# NRC7394-RX.net
KiCad netlist of a schematic drawn in Altium Designer
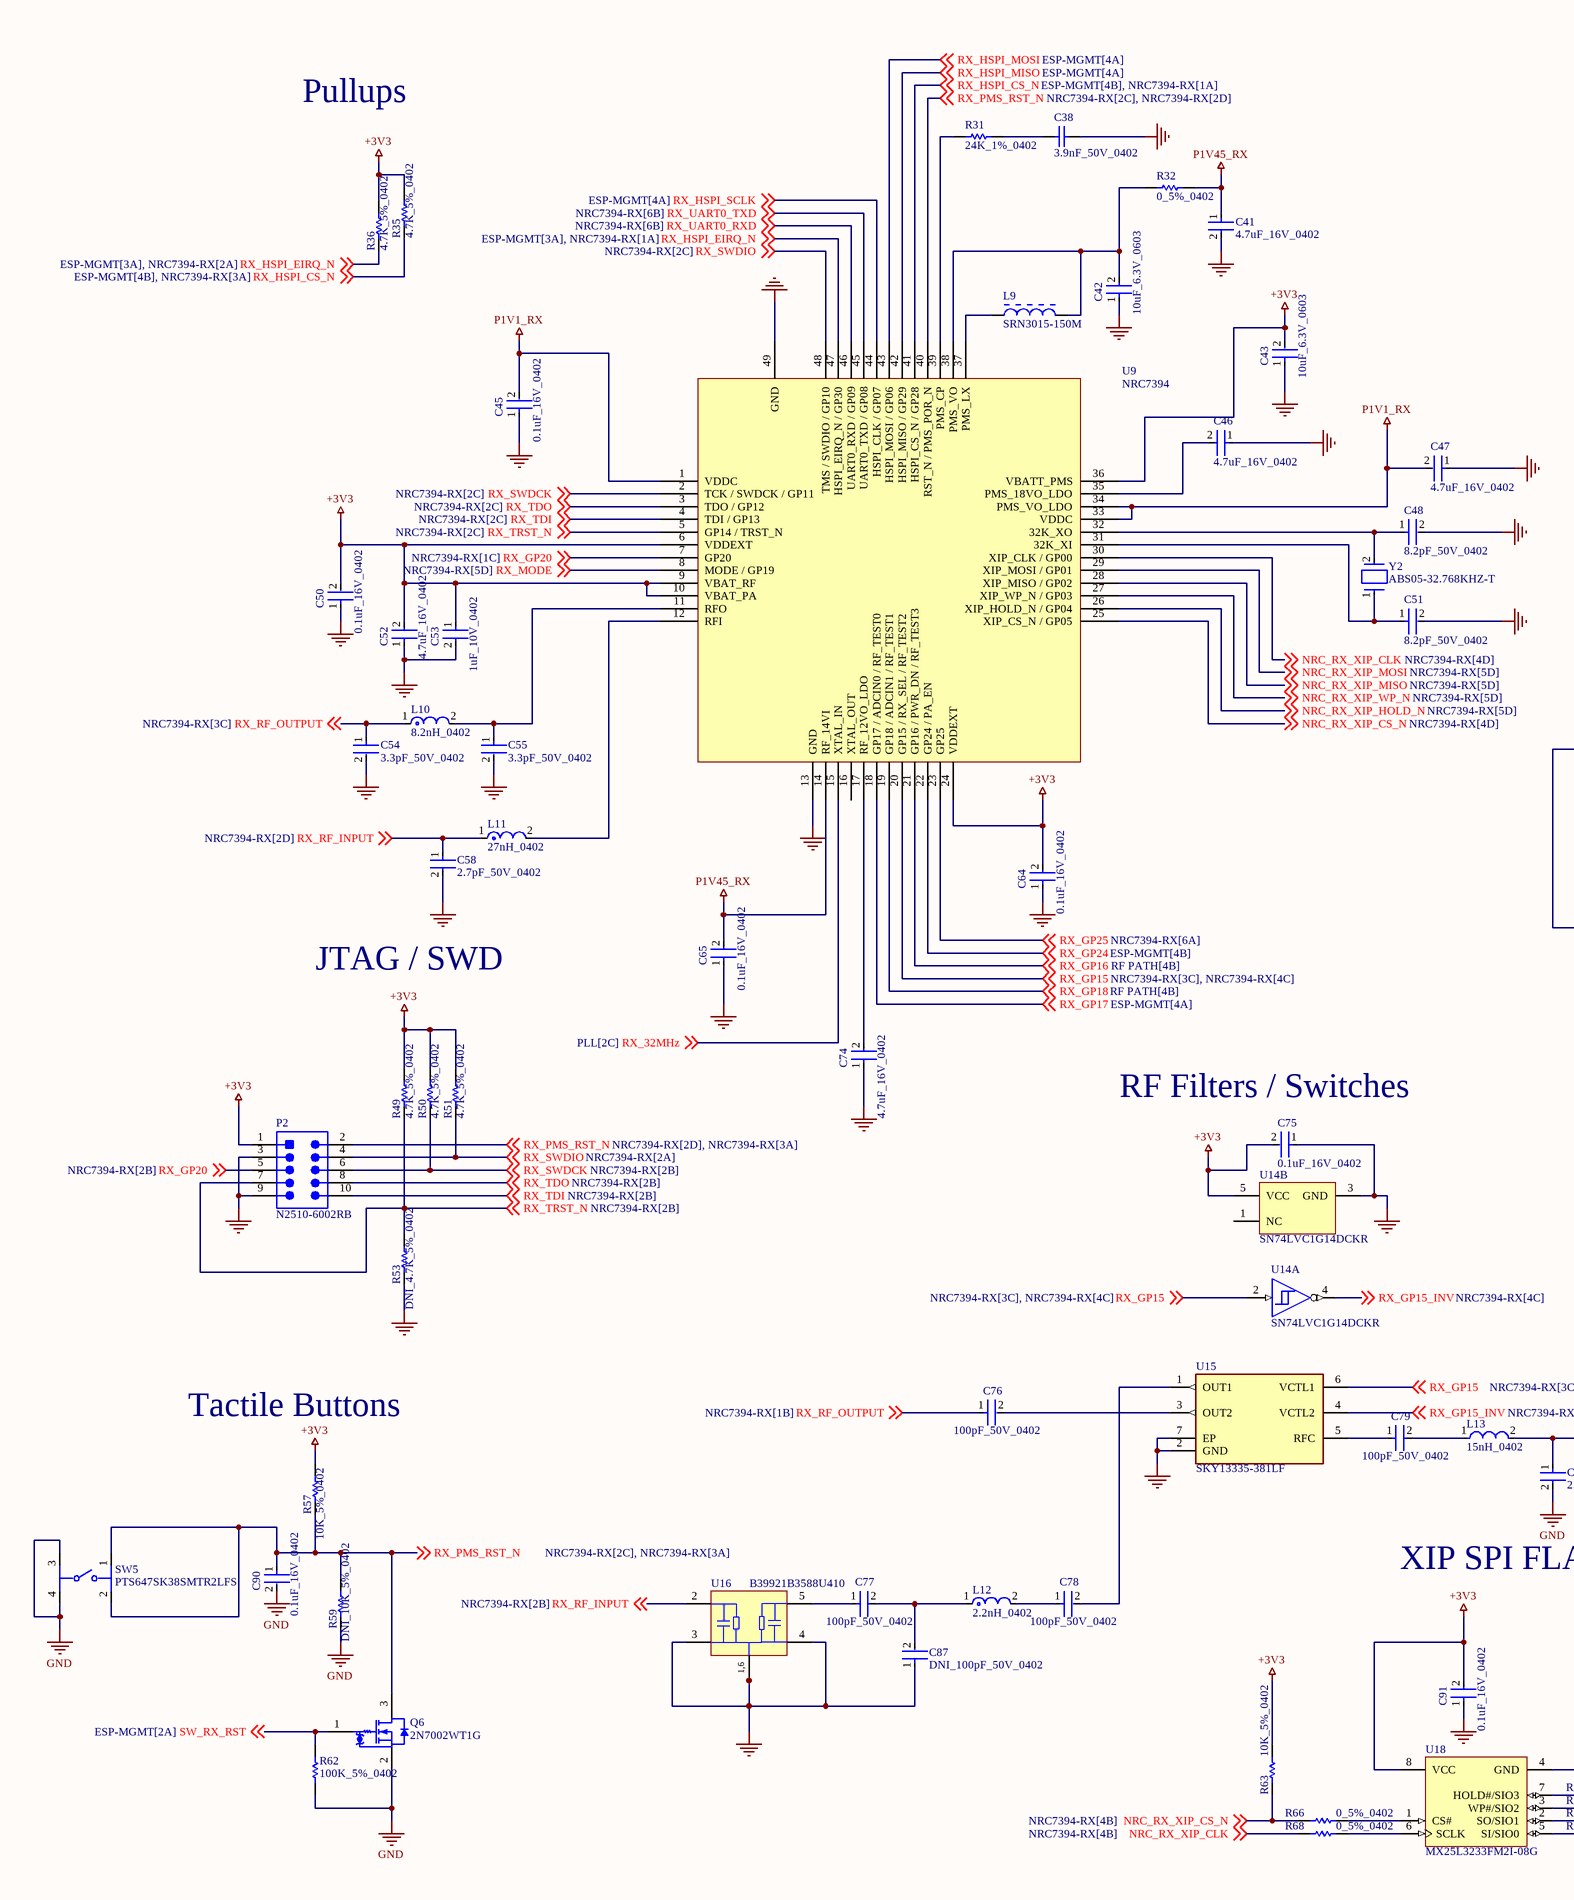
[diagram p0: NRC7394-RX.SchDoc, left]
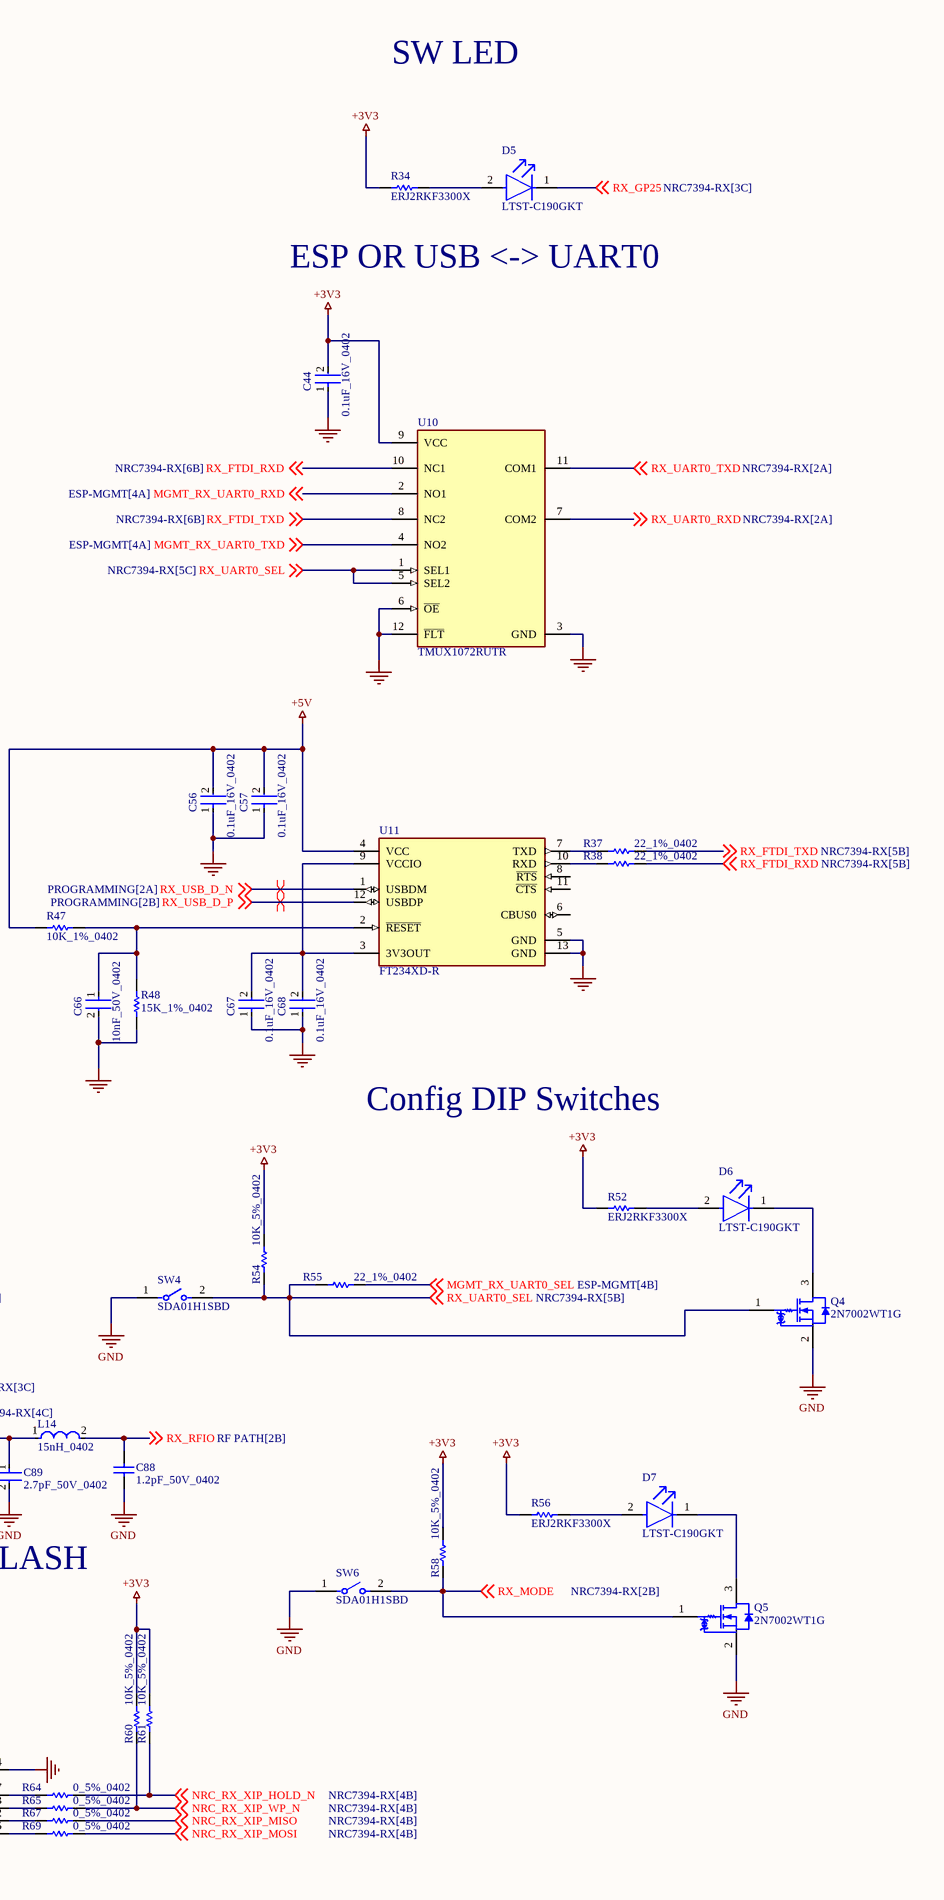
[diagram p1: NRC7394-RX.SchDoc, right]

(export (version "E")
  (design (tool "Eeschema 10.0.6"))
  (components
    (comp (ref "C38")
      (value "3.9nF_50V_0402")
      (footprint "CAPC1005X56X25LL10T15")
      (fields
        (field (name "MANUFACTURER") "AVX Interconnect / Elco")
        (field (name "PART NUMBER") "04025C392JAT2A")
      )
      (libsource (lib "Altium Content Vault") (part "CAP"))
    )
    (comp (ref "C41")
      (value "4.7uF_16V_0402")
      (footprint "FP-CL829-IPC_C")
      (description "Cap Ceramic 4.7uF 16V X5R ±20% SMD 0402 +85°C Paper T/R")
      (fields (field (name "TOLERANCE") "20%"))
      (libsource (lib "Altium Content Vault") (part "b4654b650e69147ec39a6b967a45e02"))
    )
    (comp (ref "C42")
      (value "10uF_6.3V_0603")
      (footprint "FP-GRM188-0_1-e0_2_0_55-IPC_A")
      (description "Chip Multilayer Ceramic Capacitors for General Purpose, 0603, 10uF, X5R, 15%, 20%, 6.3V")
      (fields (field (name "VOLTAGE") "6.3V") (field (name "TOLERANCE") "20%"))
      (libsource (lib "Altium Content Vault") (part "02cd4be3c70576c341d710602a673aa"))
    )
    (comp (ref "C43")
      (value "10uF_6.3V_0603")
      (footprint "FP-GRM188-0_1-e0_2_0_55-IPC_A")
      (description "Chip Multilayer Ceramic Capacitors for General Purpose, 0603, 10uF, X5R, 15%, 20%, 6.3V")
      (fields (field (name "VOLTAGE") "6.3V") (field (name "TOLERANCE") "20%"))
      (libsource (lib "Altium Content Vault") (part "02cd4be3c70576c341d710602a673aa"))
    )
    (comp (ref "C44")
      (value "0.1uF_16V_0402")
      (footprint "FP-C0402-BB-MFG")
      (description "CAP CER 0.1UF 16V 20% X7R 0402")
      (fields
        (field (name "MANUFACTURER") "Kemet")
        (field (name "OCTOPART") "https://octopart.com/c0402c104m4ractu-kemet-10476575")
      )
      (libsource (lib "Altium Content Vault") (part "b4654b650e69147ec39a6b967a45e02"))
    )
    (comp (ref "C45")
      (value "0.1uF_16V_0402")
      (footprint "FP-C0402-BB-MFG")
      (description "CAP CER 0.1UF 16V 20% X7R 0402")
      (fields
        (field (name "MANUFACTURER") "Kemet")
        (field (name "OCTOPART") "https://octopart.com/c0402c104m4ractu-kemet-10476575")
      )
      (libsource (lib "Altium Content Vault") (part "b4654b650e69147ec39a6b967a45e02"))
    )
    (comp (ref "C46")
      (value "4.7uF_16V_0402")
      (footprint "FP-CL829-IPC_C")
      (description "Cap Ceramic 4.7uF 16V X5R ±20% SMD 0402 +85°C Paper T/R")
      (fields (field (name "TOLERANCE") "20%"))
      (libsource (lib "Altium Content Vault") (part "b4654b650e69147ec39a6b967a45e02"))
    )
    (comp (ref "C47")
      (value "4.7uF_16V_0402")
      (footprint "FP-CL829-IPC_C")
      (description "Cap Ceramic 4.7uF 16V X5R ±20% SMD 0402 +85°C Paper T/R")
      (fields (field (name "TOLERANCE") "20%"))
      (libsource (lib "Altium Content Vault") (part "b4654b650e69147ec39a6b967a45e02"))
    )
    (comp (ref "C48")
      (value "8.2pF_50V_0402")
      (footprint "FP-C0402-BB-MFG")
      (description "CAP CER 8.2PF 50V NP0 0402")
      (fields
        (field (name "MANUFACTURER PART NUMBER") "C0402C829C5GACTU")
        (field (name "TOLERANCE") "0.25 pF")
      )
      (libsource (lib "Altium Content Vault") (part "b4654b650e69147ec39a6b967a45e02"))
    )
    (comp (ref "C50")
      (value "0.1uF_16V_0402")
      (footprint "FP-C0402-BB-MFG")
      (description "CAP CER 0.1UF 16V 20% X7R 0402")
      (fields
        (field (name "MANUFACTURER") "Kemet")
        (field (name "OCTOPART") "https://octopart.com/c0402c104m4ractu-kemet-10476575")
      )
      (libsource (lib "Altium Content Vault") (part "b4654b650e69147ec39a6b967a45e02"))
    )
    (comp (ref "C51")
      (value "8.2pF_50V_0402")
      (footprint "FP-C0402-BB-MFG")
      (description "CAP CER 8.2PF 50V NP0 0402")
      (fields
        (field (name "MANUFACTURER PART NUMBER") "C0402C829C5GACTU")
        (field (name "TOLERANCE") "0.25 pF")
      )
      (libsource (lib "Altium Content Vault") (part "b4654b650e69147ec39a6b967a45e02"))
    )
    (comp (ref "C52")
      (value "4.7uF_16V_0402")
      (footprint "FP-CL829-IPC_C")
      (description "Cap Ceramic 4.7uF 16V X5R ±20% SMD 0402 +85°C Paper T/R")
      (fields (field (name "TOLERANCE") "20%"))
      (libsource (lib "Altium Content Vault") (part "b4654b650e69147ec39a6b967a45e02"))
    )
    (comp (ref "C53")
      (value "1uF_10V_0402")
      (footprint "FP-C0402C105K8PACTU-MFG")
      (description "CAP CER 1UF 10V X5R 0402")
      (fields (field (name "VOLTAGE") "10V") (field (name "TOLERANCE") "10%"))
      (libsource (lib "Altium Content Vault") (part "11868f565c42a9108669ba33697ecf6"))
    )
    (comp (ref "C54")
      (value "3.3pF_50V_0402")
      (footprint "FP-C0402-BB-MFG")
      (description "Capacitor: ceramic; MLCC; 3.3pF; 50VDC; C0G; ±0.25pF; SMD; 0402")
      (fields
        (field (name "MANUFACTURER PART NUMBER") "C0402C339C5GACTU")
        (field (name "TOLERANCE") "0.25 pF")
      )
      (libsource (lib "Altium Content Vault") (part "b4654b650e69147ec39a6b967a45e02"))
    )
    (comp (ref "C55")
      (value "3.3pF_50V_0402")
      (footprint "FP-C0402-BB-MFG")
      (description "Capacitor: ceramic; MLCC; 3.3pF; 50VDC; C0G; ±0.25pF; SMD; 0402")
      (fields
        (field (name "MANUFACTURER PART NUMBER") "C0402C339C5GACTU")
        (field (name "TOLERANCE") "0.25 pF")
      )
      (libsource (lib "Altium Content Vault") (part "b4654b650e69147ec39a6b967a45e02"))
    )
    (comp (ref "C56")
      (value "0.1uF_16V_0402")
      (footprint "FP-C0402-BB-MFG")
      (description "CAP CER 0.1UF 16V 20% X7R 0402")
      (fields
        (field (name "MANUFACTURER") "Kemet")
        (field (name "OCTOPART") "https://octopart.com/c0402c104m4ractu-kemet-10476575")
      )
      (libsource (lib "Altium Content Vault") (part "b4654b650e69147ec39a6b967a45e02"))
    )
    (comp (ref "C57")
      (value "0.1uF_16V_0402")
      (footprint "FP-C0402-BB-MFG")
      (description "CAP CER 0.1UF 16V 20% X7R 0402")
      (fields
        (field (name "MANUFACTURER") "Kemet")
        (field (name "OCTOPART") "https://octopart.com/c0402c104m4ractu-kemet-10476575")
      )
      (libsource (lib "Altium Content Vault") (part "b4654b650e69147ec39a6b967a45e02"))
    )
    (comp (ref "C58")
      (value "2.7pF_50V_0402")
      (footprint "FP-GJM155-0_05-IPC_A")
      (description "Multi-Layer Ceramic Capacitor 2.7pF C0G  ±0.1pF 0402 Paper T/R")
      (fields (field (name "VOLTAGE") "50V"))
      (libsource (lib "Altium Content Vault") (part "02cd4be3c70576c341d710602a673aa"))
    )
    (comp (ref "C64")
      (value "0.1uF_16V_0402")
      (footprint "FP-C0402-BB-MFG")
      (description "CAP CER 0.1UF 16V 20% X7R 0402")
      (fields
        (field (name "MANUFACTURER") "Kemet")
        (field (name "OCTOPART") "https://octopart.com/c0402c104m4ractu-kemet-10476575")
      )
      (libsource (lib "Altium Content Vault") (part "b4654b650e69147ec39a6b967a45e02"))
    )
    (comp (ref "C65")
      (value "0.1uF_16V_0402")
      (footprint "FP-C0402-BB-MFG")
      (description "CAP CER 0.1UF 16V 20% X7R 0402")
      (fields
        (field (name "MANUFACTURER") "Kemet")
        (field (name "OCTOPART") "https://octopart.com/c0402c104m4ractu-kemet-10476575")
      )
      (libsource (lib "Altium Content Vault") (part "b4654b650e69147ec39a6b967a45e02"))
    )
    (comp (ref "C66")
      (value "10nF_50V_0402")
      (footprint "FP-CL165-IPC_C")
      (description "Cap Ceramic 10nF 50V X7R ±10% SMD 0402 +125°C Paper T/R")
      (fields (field (name "VOLTAGE") "50V") (field (name "TOLERANCE") "10%"))
      (libsource (lib "Altium Content Vault") (part "b4654b650e69147ec39a6b967a45e02"))
    )
    (comp (ref "C67")
      (value "0.1uF_16V_0402")
      (footprint "FP-C0402-BB-MFG")
      (description "CAP CER 0.1UF 16V 20% X7R 0402")
      (fields
        (field (name "MANUFACTURER") "Kemet")
        (field (name "OCTOPART") "https://octopart.com/c0402c104m4ractu-kemet-10476575")
      )
      (libsource (lib "Altium Content Vault") (part "b4654b650e69147ec39a6b967a45e02"))
    )
    (comp (ref "C68")
      (value "0.1uF_16V_0402")
      (footprint "FP-C0402-BB-MFG")
      (description "CAP CER 0.1UF 16V 20% X7R 0402")
      (fields
        (field (name "MANUFACTURER") "Kemet")
        (field (name "OCTOPART") "https://octopart.com/c0402c104m4ractu-kemet-10476575")
      )
      (libsource (lib "Altium Content Vault") (part "b4654b650e69147ec39a6b967a45e02"))
    )
    (comp (ref "C74")
      (value "4.7uF_16V_0402")
      (footprint "FP-CL829-IPC_C")
      (description "Cap Ceramic 4.7uF 16V X5R ±20% SMD 0402 +85°C Paper T/R")
      (fields (field (name "TOLERANCE") "20%"))
      (libsource (lib "Altium Content Vault") (part "b4654b650e69147ec39a6b967a45e02"))
    )
    (comp (ref "C75")
      (value "0.1uF_16V_0402")
      (footprint "FP-C0402-BB-MFG")
      (description "CAP CER 0.1UF 16V 20% X7R 0402")
      (fields
        (field (name "MANUFACTURER") "Kemet")
        (field (name "OCTOPART") "https://octopart.com/c0402c104m4ractu-kemet-10476575")
      )
      (libsource (lib "Altium Content Vault") (part "b4654b650e69147ec39a6b967a45e02"))
    )
    (comp (ref "C76")
      (value "100pF_50V_0402")
      (footprint "FP-C0402-BB-MFG")
      (description "CAP CER 100PF 50V C0G/NP0 0402")
      (fields (field (name "MANUFACTURER") "Kemet") (field (name "TOLERANCE") "0.05"))
      (libsource (lib "Altium Content Vault") (part "b4654b650e69147ec39a6b967a45e02"))
    )
    (comp (ref "C77")
      (value "100pF_50V_0402")
      (footprint "FP-C0402-BB-MFG")
      (description "CAP CER 100PF 50V C0G/NP0 0402")
      (fields (field (name "MANUFACTURER") "Kemet") (field (name "TOLERANCE") "0.05"))
      (libsource (lib "Altium Content Vault") (part "b4654b650e69147ec39a6b967a45e02"))
    )
    (comp (ref "C78")
      (value "100pF_50V_0402")
      (footprint "FP-C0402-BB-MFG")
      (description "CAP CER 100PF 50V C0G/NP0 0402")
      (fields (field (name "MANUFACTURER") "Kemet") (field (name "TOLERANCE") "0.05"))
      (libsource (lib "Altium Content Vault") (part "b4654b650e69147ec39a6b967a45e02"))
    )
    (comp (ref "C79")
      (value "100pF_50V_0402")
      (footprint "FP-C0402-BB-MFG")
      (description "CAP CER 100PF 50V C0G/NP0 0402")
      (fields (field (name "MANUFACTURER") "Kemet") (field (name "TOLERANCE") "0.05"))
      (libsource (lib "Altium Content Vault") (part "b4654b650e69147ec39a6b967a45e02"))
    )
    (comp (ref "C87")
      (value "DNI_100pF_50V_0402")
      (footprint "FP-C0402-BB-MFG")
      (description "CAP CER 100PF 50V C0G/NP0 0402")
      (fields (field (name "MANUFACTURER") "Kemet") (field (name "TOLERANCE") "0.05"))
      (libsource (lib "Altium Content Vault") (part "b4654b650e69147ec39a6b967a45e02"))
    )
    (comp (ref "C88")
      (value "1.2pF_50V_0402")
      (footprint "CAPC1006X50X20LL10T10")
      (fields
        (field (name "MANUFACTURER") "AVX Interconnect / Elco")
        (field (name "PART NUMBER") "04023J1R2BBSTR")
      )
      (libsource (lib "Altium Content Vault") (part "CAP"))
    )
    (comp (ref "C89")
      (value "2.7pF_50V_0402")
      (footprint "FP-GJM155-0_05-IPC_A")
      (description "Multi-Layer Ceramic Capacitor 2.7pF C0G  ±0.1pF 0402 Paper T/R")
      (fields (field (name "VOLTAGE") "50V"))
      (libsource (lib "Altium Content Vault") (part "02cd4be3c70576c341d710602a673aa"))
    )
    (comp (ref "C90")
      (value "0.1uF_16V_0402")
      (footprint "FP-C0402-BB-MFG")
      (description "CAP CER 0.1UF 16V 20% X7R 0402")
      (fields
        (field (name "MANUFACTURER") "Kemet")
        (field (name "OCTOPART") "https://octopart.com/c0402c104m4ractu-kemet-10476575")
      )
      (libsource (lib "Altium Content Vault") (part "b4654b650e69147ec39a6b967a45e02"))
    )
    (comp (ref "C91")
      (value "0.1uF_16V_0402")
      (footprint "FP-C0402-BB-MFG")
      (description "CAP CER 0.1UF 16V 20% X7R 0402")
      (fields
        (field (name "MANUFACTURER") "Kemet")
        (field (name "OCTOPART") "https://octopart.com/c0402c104m4ractu-kemet-10476575")
      )
      (libsource (lib "Altium Content Vault") (part "b4654b650e69147ec39a6b967a45e02"))
    )
    (comp (ref "D5")
      (value "LTST-C190GKT")
      (footprint "FP-LTST-C190GKT-MFG")
      (description "LED GREEN CLEAR CHIP SMD")
      (fields (field (name "VOLTAGE") "2V"))
      (libsource (lib "Altium Content Vault") (part "8706943c75ba83719d021d2fdc84c58"))
    )
    (comp (ref "D6")
      (value "LTST-C190GKT")
      (footprint "FP-LTST-C190GKT-MFG")
      (description "LED GREEN CLEAR CHIP SMD")
      (fields (field (name "VOLTAGE") "2V"))
      (libsource (lib "Altium Content Vault") (part "8706943c75ba83719d021d2fdc84c58"))
    )
    (comp (ref "D7")
      (value "LTST-C190GKT")
      (footprint "FP-LTST-C190GKT-MFG")
      (description "LED GREEN CLEAR CHIP SMD")
      (fields (field (name "VOLTAGE") "2V"))
      (libsource (lib "Altium Content Vault") (part "8706943c75ba83719d021d2fdc84c58"))
    )
    (comp (ref "L9")
      (value "SRN3015-150M")
      (footprint "BOUR-SRN3015-2_V")
      (fields (field (name "MANUFACTURER") "Bourns"))
      (libsource (lib "Altium Content Vault") (part "BOUR-IND-2A"))
    )
    (comp (ref "L10")
      (value "8.2nH_0402")
      (footprint "FP-LQG15HH_02-IPC_B")
      (description "Multilayer type RF Inductor 8.2nH ±5% 0.24Ω 550mA 0402")
      (fields (field (name "TOLERANCE") "5%"))
      (libsource (lib "Altium Content Vault") (part "4cc4b267dca4c8e51f7102f422741d8"))
    )
    (comp (ref "L11")
      (value "27nH_0402")
      (footprint "FP-LQG15HH_02-IPC_C")
      (description "Multilayer type RF Inductor 27nH ±5% 0.46Ω 350mA 0402")
      (fields (field (name "TOLERANCE") "5%"))
      (libsource (lib "Altium Content Vault") (part "4cc4b267dca4c8e51f7102f422741d8"))
    )
    (comp (ref "L12")
      (value "2.2nH_0402")
      (footprint "FP-LQG15HH_02-IPC_C")
      (description "Multilayer type RF Inductor 2.2nH ±0.3nH 0.09Ω 900mA 0402")
      (libsource (lib "Altium Content Vault") (part "4cc4b267dca4c8e51f7102f422741d8"))
    )
    (comp (ref "L13")
      (value "15nH_0402")
      (footprint "FP-HK1005-MFG")
      (description "FIXED IND 15NH 320MA 460 MOHM")
      (fields (field (name "TOLERANCE") "5%"))
      (libsource (lib "Altium Content Vault") (part "725321dda6339637d4d059423bc1c3c"))
    )
    (comp (ref "L14")
      (value "15nH_0402")
      (footprint "FP-HK1005-MFG")
      (description "FIXED IND 15NH 320MA 460 MOHM")
      (fields (field (name "TOLERANCE") "5%"))
      (libsource (lib "Altium Content Vault") (part "725321dda6339637d4d059423bc1c3c"))
    )
    (comp (ref "P2")
      (value "N2510-6002RB")
      (footprint "3M-N2510-6002-10_V")
      (fields (field (name "PARTNUMBER") "N2510") (field (name "MANUFACTURER") "3M"))
      (libsource (lib "Altium Content Vault") (part "CN-2P-M-R10"))
    )
    (comp (ref "Q4")
      (value "2N7002WT1G")
      (footprint "ONSC-SC-70-3-419-04_V")
      (description "Small Signal MOSFET, 60 V, 340 mA, Single, N-Channel, 3-Pin SC70, Pb-Free, Tape and Reel")
      (fields (field (name "MANUFACTURER") "On Semiconductor"))
      (libsource (lib "Altium Content Vault") (part "ONSC-NMOS-G1S2D3-3_C"))
    )
    (comp (ref "Q5")
      (value "2N7002WT1G")
      (footprint "ONSC-SC-70-3-419-04_V")
      (description "Small Signal MOSFET, 60 V, 340 mA, Single, N-Channel, 3-Pin SC70, Pb-Free, Tape and Reel")
      (fields (field (name "MANUFACTURER") "On Semiconductor"))
      (libsource (lib "Altium Content Vault") (part "ONSC-NMOS-G1S2D3-3_C"))
    )
    (comp (ref "Q6")
      (value "2N7002WT1G")
      (footprint "ONSC-SC-70-3-419-04_V")
      (description "Small Signal MOSFET, 60 V, 340 mA, Single, N-Channel, 3-Pin SC70, Pb-Free, Tape and Reel")
      (fields (field (name "MANUFACTURER") "On Semiconductor"))
      (libsource (lib "Altium Content Vault") (part "ONSC-NMOS-G1S2D3-3_C"))
    )
    (comp (ref "R31")
      (value "24K_1%_0402")
      (footprint "RESC1005X40X25ML05T05")
      (fields (field (name "PART NUMBER") "CRCW040224K0FKED") (field (name "MANUFACTURER") "Vishay Dale"))
      (libsource (lib "Altium Content Vault") (part "RES"))
    )
    (comp (ref "R32")
      (value "0_5%_0402")
      (footprint "RESC1005X40X25ML05T10")
      (fields (field (name "MANUFACTURER") "Panasonic") (field (name "PART NUMBER") "ERJ-U020R00X"))
      (libsource (lib "Altium Content Vault") (part "RES"))
    )
    (comp (ref "R34")
      (value "ERJ2RKF3300X")
      (footprint "RESC1005X40X25ML05T05")
      (fields (field (name "MANUFACTURER") "Panasonic"))
      (libsource (lib "Altium Content Vault") (part "RES"))
    )
    (comp (ref "R35")
      (value "4.7K_5%_0402")
      (footprint "RESC1005X40X25LL05T05")
      (fields (field (name "PART NUMBER") "CRCW04024K70JNTD") (field (name "MANUFACTURER") "Vishay Dale"))
      (libsource (lib "Altium Content Vault") (part "RES"))
    )
    (comp (ref "R36")
      (value "4.7K_5%_0402")
      (footprint "RESC1005X40X25LL05T05")
      (fields (field (name "PART NUMBER") "CRCW04024K70JNTD") (field (name "MANUFACTURER") "Vishay Dale"))
      (libsource (lib "Altium Content Vault") (part "RES"))
    )
    (comp (ref "R37")
      (value "22_1%_0402")
      (footprint "RESC1005X40X25LL05T10")
      (fields (field (name "MANUFACTURER") "Yageo / Phycomp") (field (name "PART NUMBER") "RC0402FR-0722RL"))
      (libsource (lib "Altium Content Vault") (part "RES"))
    )
    (comp (ref "R38")
      (value "22_1%_0402")
      (footprint "RESC1005X40X25LL05T10")
      (fields (field (name "MANUFACTURER") "Yageo / Phycomp") (field (name "PART NUMBER") "RC0402FR-0722RL"))
      (libsource (lib "Altium Content Vault") (part "RES"))
    )
    (comp (ref "R47")
      (value "10K_1%_0402")
      (footprint "RESC1005X40X25NL05T10")
      (fields (field (name "MANUFACTURER") "Multicomp") (field (name "PART NUMBER") "MCMR04X103 JTL"))
      (libsource (lib "Altium Content Vault") (part "RES"))
    )
    (comp (ref "R48")
      (value "15K_1%_0402")
      (footprint "RESC1005X40X25ML05T10")
      (fields (field (name "MANUFACTURER") "Yageo") (field (name "PART NUMBER") "RC0402JR-1315KL"))
      (libsource (lib "Altium Content Vault") (part "RES"))
    )
    (comp (ref "R49")
      (value "4.7K_5%_0402")
      (footprint "RESC1005X40X25LL05T05")
      (fields (field (name "PART NUMBER") "CRCW04024K70JNTD") (field (name "MANUFACTURER") "Vishay Dale"))
      (libsource (lib "Altium Content Vault") (part "RES"))
    )
    (comp (ref "R50")
      (value "4.7K_5%_0402")
      (footprint "RESC1005X40X25LL05T05")
      (fields (field (name "PART NUMBER") "CRCW04024K70JNTD") (field (name "MANUFACTURER") "Vishay Dale"))
      (libsource (lib "Altium Content Vault") (part "RES"))
    )
    (comp (ref "R51")
      (value "4.7K_5%_0402")
      (footprint "RESC1005X40X25LL05T05")
      (fields (field (name "PART NUMBER") "CRCW04024K70JNTD") (field (name "MANUFACTURER") "Vishay Dale"))
      (libsource (lib "Altium Content Vault") (part "RES"))
    )
    (comp (ref "R52")
      (value "ERJ2RKF3300X")
      (footprint "RESC1005X40X25ML05T05")
      (fields (field (name "MANUFACTURER") "Panasonic"))
      (libsource (lib "Altium Content Vault") (part "RES"))
    )
    (comp (ref "R53")
      (value "DNI_4.7K_5%_0402")
      (footprint "RESC1005X40X25LL05T05")
      (fields (field (name "PART NUMBER") "CRCW04024K70JNTD") (field (name "MANUFACTURER") "Vishay Dale"))
      (libsource (lib "Altium Content Vault") (part "RES"))
    )
    (comp (ref "R54")
      (value "10K_5%_0402")
      (footprint "RESC1005X40X25ML05T05")
      (fields (field (name "MANUFACTURER") "Panasonic") (field (name "PART NUMBER") "ERT-J0EM103J"))
      (libsource (lib "Altium Content Vault") (part "RES"))
    )
    (comp (ref "R55")
      (value "22_1%_0402")
      (footprint "RESC1005X40X25LL05T10")
      (fields (field (name "MANUFACTURER") "Yageo / Phycomp") (field (name "PART NUMBER") "RC0402FR-0722RL"))
      (libsource (lib "Altium Content Vault") (part "RES"))
    )
    (comp (ref "R56")
      (value "ERJ2RKF3300X")
      (footprint "RESC1005X40X25ML05T05")
      (fields (field (name "MANUFACTURER") "Panasonic"))
      (libsource (lib "Altium Content Vault") (part "RES"))
    )
    (comp (ref "R57")
      (value "10K_5%_0402")
      (footprint "RESC1005X40X25ML05T05")
      (fields (field (name "MANUFACTURER") "Panasonic") (field (name "PART NUMBER") "ERT-J0EM103J"))
      (libsource (lib "Altium Content Vault") (part "RES"))
    )
    (comp (ref "R58")
      (value "10K_5%_0402")
      (footprint "RESC1005X40X25ML05T05")
      (fields (field (name "MANUFACTURER") "Panasonic") (field (name "PART NUMBER") "ERT-J0EM103J"))
      (libsource (lib "Altium Content Vault") (part "RES"))
    )
    (comp (ref "R59")
      (value "DNI_10K_5%_0402")
      (footprint "RESC1005X40X25ML05T05")
      (fields (field (name "MANUFACTURER") "Panasonic") (field (name "PART NUMBER") "ERT-J0EM103J"))
      (libsource (lib "Altium Content Vault") (part "RES"))
    )
    (comp (ref "R60")
      (value "10K_5%_0402")
      (footprint "RESC1005X40X25ML05T05")
      (fields (field (name "MANUFACTURER") "Panasonic") (field (name "PART NUMBER") "ERT-J0EM103J"))
      (libsource (lib "Altium Content Vault") (part "RES"))
    )
    (comp (ref "R61")
      (value "10K_5%_0402")
      (footprint "RESC1005X40X25ML05T05")
      (fields (field (name "MANUFACTURER") "Panasonic") (field (name "PART NUMBER") "ERT-J0EM103J"))
      (libsource (lib "Altium Content Vault") (part "RES"))
    )
    (comp (ref "R62")
      (value "100K_5%_0402")
      (footprint "RESC1005X37X25ML05T10")
      (fields (field (name "PART NUMBER") "RE0402DR-07100KL") (field (name "MANUFACTURER") "Yageo / Phycomp"))
      (libsource (lib "Altium Content Vault") (part "RES"))
    )
    (comp (ref "R63")
      (value "10K_5%_0402")
      (footprint "RESC1005X40X25ML05T05")
      (fields (field (name "MANUFACTURER") "Panasonic") (field (name "PART NUMBER") "ERT-J0EM103J"))
      (libsource (lib "Altium Content Vault") (part "RES"))
    )
    (comp (ref "R64")
      (value "0_5%_0402")
      (footprint "RESC1005X40X25ML05T10")
      (fields (field (name "MANUFACTURER") "Panasonic") (field (name "PART NUMBER") "ERJ-U020R00X"))
      (libsource (lib "Altium Content Vault") (part "RES"))
    )
    (comp (ref "R65")
      (value "0_5%_0402")
      (footprint "RESC1005X40X25ML05T10")
      (fields (field (name "MANUFACTURER") "Panasonic") (field (name "PART NUMBER") "ERJ-U020R00X"))
      (libsource (lib "Altium Content Vault") (part "RES"))
    )
    (comp (ref "R66")
      (value "0_5%_0402")
      (footprint "RESC1005X40X25ML05T10")
      (fields (field (name "MANUFACTURER") "Panasonic") (field (name "PART NUMBER") "ERJ-U020R00X"))
      (libsource (lib "Altium Content Vault") (part "RES"))
    )
    (comp (ref "R67")
      (value "0_5%_0402")
      (footprint "RESC1005X40X25ML05T10")
      (fields (field (name "MANUFACTURER") "Panasonic") (field (name "PART NUMBER") "ERJ-U020R00X"))
      (libsource (lib "Altium Content Vault") (part "RES"))
    )
    (comp (ref "R68")
      (value "0_5%_0402")
      (footprint "RESC1005X40X25ML05T10")
      (fields (field (name "MANUFACTURER") "Panasonic") (field (name "PART NUMBER") "ERJ-U020R00X"))
      (libsource (lib "Altium Content Vault") (part "RES"))
    )
    (comp (ref "R69")
      (value "0_5%_0402")
      (footprint "RESC1005X40X25ML05T10")
      (fields (field (name "MANUFACTURER") "Panasonic") (field (name "PART NUMBER") "ERJ-U020R00X"))
      (libsource (lib "Altium Content Vault") (part "RES"))
    )
    (comp (ref "SW4")
      (value "SDA01H1SBD")
      (footprint "FP-SDA01H1SBD-MFG")
      (description "SWITCH SLIDE DIP SPST 25MA 24V")
      (fields
        (field (name "OCTOPART") "https://octopart.com/sda01h1sbd-c%26k+components-7089741")
        (field (name "MANUFACTURER") "C&K Components")
      )
      (libsource (lib "Altium Content Vault") (part "bb27bde45df87f1f469753f287ef5ae"))
    )
    (comp (ref "SW5")
      (value "PTS647SK38SMTR2LFS")
      (footprint "FP-PTS647SK38SMTR2LFS-MFG")
      (description "TACT 4.5 X 4.5, 3.8 MM H, 2.5N,")
      (libsource (lib "Altium Content Vault") (part "1adf0dd01260c80cf25a44bfd6b99ba"))
    )
    (comp (ref "SW6")
      (value "SDA01H1SBD")
      (footprint "FP-SDA01H1SBD-MFG")
      (description "SWITCH SLIDE DIP SPST 25MA 24V")
      (fields
        (field (name "OCTOPART") "https://octopart.com/sda01h1sbd-c%26k+components-7089741")
        (field (name "MANUFACTURER") "C&K Components")
      )
      (libsource (lib "Altium Content Vault") (part "bb27bde45df87f1f469753f287ef5ae"))
    )
    (comp (ref "U9")
      (value "NRC7394")
      (footprint "QFN48_6X6")
      (description "NRC7394 WiFi HaLow chipset")
      (libsource (lib "NRC7394") (part "NRC7394"))
    )
    (comp (ref "U10")
      (value "TMUX1072RUTR")
      (footprint "FP-RUT0012A-MFG")
      (description "IC SWITCH SPDT DUAL 12UQFN")
      (libsource (lib "Altium Content Vault") (part "12a319ab100cd6cfe745e35972674f5"))
    )
    (comp (ref "U11")
      (value "FT234XD-R")
      (footprint "FP-DFN-12-IPC_B")
      (description "IC USB SERIAL BASIC UART 12DFN")
      (libsource (lib "Altium Content Vault") (part "4bef3367ed9f9051bcb84ab46edda1c"))
    )
    (comp (ref "U14")
      (value "SN74LVC1G14DCKR")
      (footprint "DCK0005A_L")
      (description "Single Schmitt-Trigger Inverter, DCK0005A, LARGE T&R")
      (fields
        (field (name "GENERIC PART NUMBER") "SN74LVC1G14")
        (field (name "MANUFACTURER") "Texas Instruments")
      )
      (libsource (lib "") (part "TI-SN74XXX1XX4-XX-5-SCHMITT_1"))
    )
    (comp (ref "U15")
      (value "SKY13335-381LF")
      (footprint "FP-SKY13335-381LF-MFG")
      (description "IC RF SWITCH SPDT 6GHZ 6MLPD")
      (libsource (lib "Altium Content Vault") (part "beb9d273cf817256a5bcdae75b1af25"))
    )
    (comp (ref "U16")
      (value "B39921B3588U410")
      (footprint "EPCO-DCC6C-6")
      (description "SAW RF Filter, 915 MHz, -45 to 125 degC, 6-Pin SMD, RoHS, Tape and Reel")
      (fields (field (name "MANUFACTURER") "EPCOS"))
      (libsource (lib "Altium Content Vault") (part "EPCO-B3588-6"))
    )
    (comp (ref "U18")
      (value "MX25L3233FM2I-08G")
      (footprint "MXIC-SOP-8_M")
      (fields (field (name "MANUFACTURER") "Macronix"))
      (libsource (lib "Altium Content Vault") (part "MXIC-MX25L3233FM2I-08G-SOP-8"))
    )
    (comp (ref "Y2")
      (value "ABS05-32.768KHZ-T")
      (footprint "FP-ABS05-MFG")
      (description "Crystal 32.768kHz ±20ppm (Tol) 12.5pF FUND 90kΩ 2-Pin SMD T/R")
      (fields (field (name "TOLERANCE") "20ppm"))
      (libsource (lib "Altium Content Vault") (part "c23a69dc6c9e2f18f2079038eb95dd1"))
    )
  )
  (nets
    (net (code "1") (name "+3V3") (class "Default")
      (node (ref "C43") (pin "2") (pinfunction "2_2") (pintype "passive"))
      (node (ref "C44") (pin "2") (pinfunction "2_2") (pintype "passive"))
      (node (ref "C50") (pin "2") (pinfunction "2_2") (pintype "passive"))
      (node (ref "C52") (pin "2") (pinfunction "2_2") (pintype "passive"))
      (node (ref "C53") (pin "1") (pinfunction "1_1") (pintype "passive"))
      (node (ref "C64") (pin "2") (pinfunction "2_2") (pintype "passive"))
      (node (ref "C75") (pin "2") (pinfunction "2_2") (pintype "passive"))
      (node (ref "C91") (pin "2") (pinfunction "2_2") (pintype "passive"))
      (node (ref "P2") (pin "1") (pinfunction "1_1") (pintype "passive"))
      (node (ref "R34") (pin "1") (pinfunction "1_1") (pintype "passive"))
      (node (ref "R35") (pin "2") (pinfunction "2_2") (pintype "passive"))
      (node (ref "R36") (pin "2") (pinfunction "2_2") (pintype "passive"))
      (node (ref "R49") (pin "2") (pinfunction "2_2") (pintype "passive"))
      (node (ref "R50") (pin "2") (pinfunction "2_2") (pintype "passive"))
      (node (ref "R51") (pin "2") (pinfunction "2_2") (pintype "passive"))
      (node (ref "R52") (pin "1") (pinfunction "1_1") (pintype "passive"))
      (node (ref "R54") (pin "2") (pinfunction "2_2") (pintype "passive"))
      (node (ref "R56") (pin "1") (pinfunction "1_1") (pintype "passive"))
      (node (ref "R57") (pin "2") (pinfunction "2_2") (pintype "passive"))
      (node (ref "R58") (pin "2") (pinfunction "2_2") (pintype "passive"))
      (node (ref "R60") (pin "2") (pinfunction "2_2") (pintype "passive"))
      (node (ref "R61") (pin "2") (pinfunction "2_2") (pintype "passive"))
      (node (ref "R63") (pin "2") (pinfunction "2_2") (pintype "passive"))
      (node (ref "U10") (pin "9") (pinfunction "VCC_9") (pintype "power_in"))
      (node (ref "U14") (pin "5") (pinfunction "VCC_5") (pintype "power_in"))
      (node (ref "U18") (pin "8") (pinfunction "VCC_8") (pintype "power_in"))
      (node (ref "U9") (pin "10") (pinfunction "VBAT_PA_10") (pintype "passive"))
      (node (ref "U9") (pin "24") (pinfunction "VDDEXT_24") (pintype "passive"))
      (node (ref "U9") (pin "36") (pinfunction "VBATT_PMS_36") (pintype "passive"))
      (node (ref "U9") (pin "6") (pinfunction "VDDEXT_6") (pintype "passive"))
      (node (ref "U9") (pin "9") (pinfunction "VBAT_RF_9") (pintype "passive"))
    )
    (net (code "2") (name "+5V") (class "Default")
      (node (ref "C56") (pin "2") (pinfunction "2_2") (pintype "passive"))
      (node (ref "C57") (pin "2") (pinfunction "2_2") (pintype "passive"))
      (node (ref "R47") (pin "1") (pinfunction "1_1") (pintype "passive"))
      (node (ref "U11") (pin "4") (pinfunction "VCC_4") (pintype "power_in"))
    )
    (net (code "3") (name "GND") (class "Default")
      (node (ref "C38") (pin "2") (pinfunction "2_2") (pintype "passive"))
      (node (ref "C41") (pin "2") (pinfunction "2_2") (pintype "passive"))
      (node (ref "C42") (pin "1") (pinfunction "1_1") (pintype "passive"))
      (node (ref "C43") (pin "1") (pinfunction "1_1") (pintype "passive"))
      (node (ref "C44") (pin "1") (pinfunction "1_1") (pintype "passive"))
      (node (ref "C45") (pin "1") (pinfunction "1_1") (pintype "passive"))
      (node (ref "C46") (pin "1") (pinfunction "1_1") (pintype "passive"))
      (node (ref "C47") (pin "1") (pinfunction "1_1") (pintype "passive"))
      (node (ref "C48") (pin "2") (pinfunction "2_2") (pintype "passive"))
      (node (ref "C50") (pin "1") (pinfunction "1_1") (pintype "passive"))
      (node (ref "C51") (pin "2") (pinfunction "2_2") (pintype "passive"))
      (node (ref "C52") (pin "1") (pinfunction "1_1") (pintype "passive"))
      (node (ref "C53") (pin "2") (pinfunction "2_2") (pintype "passive"))
      (node (ref "C54") (pin "2") (pinfunction "2_2") (pintype "passive"))
      (node (ref "C55") (pin "2") (pinfunction "2_2") (pintype "passive"))
      (node (ref "C56") (pin "1") (pinfunction "1_1") (pintype "passive"))
      (node (ref "C57") (pin "1") (pinfunction "1_1") (pintype "passive"))
      (node (ref "C58") (pin "2") (pinfunction "2_2") (pintype "passive"))
      (node (ref "C64") (pin "1") (pinfunction "1_1") (pintype "passive"))
      (node (ref "C65") (pin "1") (pinfunction "1_1") (pintype "passive"))
      (node (ref "C66") (pin "2") (pinfunction "2_2") (pintype "passive"))
      (node (ref "C67") (pin "1") (pinfunction "1_1") (pintype "passive"))
      (node (ref "C68") (pin "1") (pinfunction "1_1") (pintype "passive"))
      (node (ref "C74") (pin "1") (pinfunction "1_1") (pintype "passive"))
      (node (ref "C75") (pin "1") (pinfunction "1_1") (pintype "passive"))
      (node (ref "C87") (pin "1") (pinfunction "1_1") (pintype "passive"))
      (node (ref "C88") (pin "1") (pinfunction "1_1") (pintype "passive"))
      (node (ref "C89") (pin "2") (pinfunction "2_2") (pintype "passive"))
      (node (ref "C90") (pin "2") (pinfunction "2_2") (pintype "passive"))
      (node (ref "C91") (pin "1") (pinfunction "1_1") (pintype "passive"))
      (node (ref "P2") (pin "3") (pinfunction "3_3") (pintype "passive"))
      (node (ref "P2") (pin "9") (pinfunction "9_9") (pintype "passive"))
      (node (ref "Q4") (pin "2") (pinfunction "S_2") (pintype "passive"))
      (node (ref "Q5") (pin "2") (pinfunction "S_2") (pintype "passive"))
      (node (ref "Q6") (pin "2") (pinfunction "S_2") (pintype "passive"))
      (node (ref "R48") (pin "1") (pinfunction "1_1") (pintype "passive"))
      (node (ref "R53") (pin "1") (pinfunction "1_1") (pintype "passive"))
      (node (ref "R59") (pin "1") (pinfunction "1_1") (pintype "passive"))
      (node (ref "R62") (pin "1") (pinfunction "1_1") (pintype "passive"))
      (node (ref "SW4") (pin "1") (pinfunction "1_1") (pintype "passive"))
      (node (ref "SW5") (pin "3") (pinfunction "3_3") (pintype "passive"))
      (node (ref "SW5") (pin "4") (pinfunction "4_4") (pintype "passive"))
      (node (ref "SW6") (pin "1") (pinfunction "1_1") (pintype "passive"))
      (node (ref "U10") (pin "12") (pinfunction "~{FLT}_12") (pintype "open_collector"))
      (node (ref "U10") (pin "3") (pinfunction "GND_3") (pintype "power_in"))
      (node (ref "U10") (pin "6") (pinfunction "~{OE}_6") (pintype "input"))
      (node (ref "U11") (pin "13") (pinfunction "GND_13") (pintype "power_in"))
      (node (ref "U11") (pin "5") (pinfunction "GND_5") (pintype "power_in"))
      (node (ref "U14") (pin "3") (pinfunction "GND_3") (pintype "power_in"))
      (node (ref "U15") (pin "2") (pinfunction "GND_2") (pintype "power_in"))
      (node (ref "U15") (pin "7") (pinfunction "EP_7") (pintype "power_in"))
      (node (ref "U16") (pin "1") (pinfunction "GND_1") (pintype "passive"))
      (node (ref "U16") (pin "3") (pinfunction "GND_3") (pintype "passive"))
      (node (ref "U16") (pin "4") (pinfunction "GND_4") (pintype "passive"))
      (node (ref "U16") (pin "6") (pinfunction "GND_6") (pintype "passive"))
      (node (ref "U18") (pin "4") (pinfunction "GND_4") (pintype "power_in"))
      (node (ref "U9") (pin "13") (pinfunction "GND_13") (pintype "passive"))
      (node (ref "U9") (pin "49") (pinfunction "GND_49") (pintype "passive"))
    )
    (net (code "4") (name "MGMT_RX_UART0_RXD") (class "Default")
      (node (ref "U10") (pin "2") (pinfunction "NO1_2") (pintype "passive"))
    )
    (net (code "5") (name "MGMT_RX_UART0_SEL") (class "Default")
      (node (ref "R55") (pin "2") (pinfunction "2_2") (pintype "passive"))
    )
    (net (code "6") (name "MGMT_RX_UART0_TXD") (class "Default")
      (node (ref "U10") (pin "4") (pinfunction "NO2_4") (pintype "passive"))
    )
    (net (code "7") (name "NRC_RX_XIP_CLK") (class "Default")
      (node (ref "R68") (pin "1") (pinfunction "1_1") (pintype "passive"))
      (node (ref "U9") (pin "30") (pinfunction "XIP_CLK_/_GP00_30") (pintype "passive"))
    )
    (net (code "8") (name "NRC_RX_XIP_CS_N") (class "Default")
      (node (ref "R63") (pin "1") (pinfunction "1_1") (pintype "passive"))
      (node (ref "R66") (pin "1") (pinfunction "1_1") (pintype "passive"))
      (node (ref "U9") (pin "25") (pinfunction "XIP_CS_N_/_GP05_25") (pintype "passive"))
    )
    (net (code "9") (name "NRC_RX_XIP_HOLD_N") (class "Default")
      (node (ref "R61") (pin "1") (pinfunction "1_1") (pintype "passive"))
      (node (ref "R64") (pin "2") (pinfunction "2_2") (pintype "passive"))
      (node (ref "U9") (pin "26") (pinfunction "XIP_HOLD_N_/_GP04_26") (pintype "passive"))
    )
    (net (code "10") (name "NRC_RX_XIP_MISO") (class "Default")
      (node (ref "R67") (pin "2") (pinfunction "2_2") (pintype "passive"))
      (node (ref "U9") (pin "28") (pinfunction "XIP_MISO_/_GP02_28") (pintype "passive"))
    )
    (net (code "11") (name "NRC_RX_XIP_MOSI") (class "Default")
      (node (ref "R69") (pin "2") (pinfunction "2_2") (pintype "passive"))
      (node (ref "U9") (pin "29") (pinfunction "XIP_MOSI_/_GP01_29") (pintype "passive"))
    )
    (net (code "12") (name "NRC_RX_XIP_WP_N") (class "Default")
      (node (ref "R60") (pin "1") (pinfunction "1_1") (pintype "passive"))
      (node (ref "R65") (pin "2") (pinfunction "2_2") (pintype "passive"))
      (node (ref "U9") (pin "27") (pinfunction "XIP_WP_N_/_GP03_27") (pintype "passive"))
    )
    (net (code "13") (name "Net-(C38-Pad1)") (class "Default")
      (node (ref "C38") (pin "1") (pinfunction "1_1") (pintype "passive"))
      (node (ref "R31") (pin "2") (pinfunction "2_2") (pintype "passive"))
    )
    (net (code "14") (name "Net-(C77-Pad2)") (class "Default")
      (node (ref "C77") (pin "2") (pinfunction "2_2") (pintype "passive"))
      (node (ref "C87") (pin "2") (pinfunction "2_2") (pintype "passive"))
      (node (ref "L12") (pin "1") (pinfunction "1_1") (pintype "passive"))
    )
    (net (code "15") (name "Net-(C78-Pad1)") (class "Default")
      (node (ref "C78") (pin "1") (pinfunction "1_1") (pintype "passive"))
      (node (ref "L12") (pin "2") (pinfunction "2_2") (pintype "passive"))
    )
    (net (code "16") (name "Net-(C79-Pad2)") (class "Default")
      (node (ref "C79") (pin "2") (pinfunction "2_2") (pintype "passive"))
      (node (ref "L13") (pin "1") (pinfunction "1_1") (pintype "passive"))
    )
    (net (code "17") (name "Net-(C89-Pad1)") (class "Default")
      (node (ref "C89") (pin "1") (pinfunction "1_1") (pintype "passive"))
      (node (ref "L13") (pin "2") (pinfunction "2_2") (pintype "passive"))
      (node (ref "L14") (pin "1") (pinfunction "1_1") (pintype "passive"))
    )
    (net (code "18") (name "Net-(D5-A)") (class "Default")
      (node (ref "D5") (pin "2") (pinfunction "A_2") (pintype "passive"))
      (node (ref "R34") (pin "2") (pinfunction "2_2") (pintype "passive"))
    )
    (net (code "19") (name "Net-(D6-A)") (class "Default")
      (node (ref "D6") (pin "2") (pinfunction "A_2") (pintype "passive"))
      (node (ref "R52") (pin "2") (pinfunction "2_2") (pintype "passive"))
    )
    (net (code "20") (name "Net-(D6-C)") (class "Default")
      (node (ref "D6") (pin "1") (pinfunction "C_1") (pintype "passive"))
      (node (ref "Q4") (pin "3") (pinfunction "D_3") (pintype "passive"))
    )
    (net (code "21") (name "Net-(D7-A)") (class "Default")
      (node (ref "D7") (pin "2") (pinfunction "A_2") (pintype "passive"))
      (node (ref "R56") (pin "2") (pinfunction "2_2") (pintype "passive"))
    )
    (net (code "22") (name "Net-(D7-C)") (class "Default")
      (node (ref "D7") (pin "1") (pinfunction "C_1") (pintype "passive"))
      (node (ref "Q5") (pin "3") (pinfunction "D_3") (pintype "passive"))
    )
    (net (code "23") (name "Net-(U9-32K_XI)") (class "Default")
      (node (ref "C51") (pin "1") (pinfunction "1_1") (pintype "passive"))
      (node (ref "U9") (pin "31") (pinfunction "32K_XI_31") (pintype "passive"))
      (node (ref "Y2") (pin "1") (pinfunction "1_1") (pintype "passive"))
    )
    (net (code "24") (name "Net-(U9-32K_XO)") (class "Default")
      (node (ref "C48") (pin "1") (pinfunction "1_1") (pintype "passive"))
      (node (ref "U9") (pin "32") (pinfunction "32K_XO_32") (pintype "passive"))
      (node (ref "Y2") (pin "2") (pinfunction "2_2") (pintype "passive"))
    )
    (net (code "25") (name "Net-(U9-PMS_18VO_LDO)") (class "Default")
      (node (ref "C46") (pin "2") (pinfunction "2_2") (pintype "passive"))
      (node (ref "U9") (pin "35") (pinfunction "PMS_18VO_LDO_35") (pintype "passive"))
    )
    (net (code "26") (name "Net-(U9-PMS_CP)") (class "Default")
      (node (ref "R31") (pin "1") (pinfunction "1_1") (pintype "passive"))
      (node (ref "U9") (pin "39") (pinfunction "PMS_CP_39") (pintype "passive"))
    )
    (net (code "27") (name "Net-(U9-PMS_LX)") (class "Default")
      (node (ref "L9") (pin "1") (pinfunction "1_1") (pintype "passive"))
      (node (ref "U9") (pin "37") (pinfunction "PMS_LX_37") (pintype "passive"))
    )
    (net (code "28") (name "Net-(U9-PMS_VO)") (class "Default")
      (node (ref "C42") (pin "2") (pinfunction "2_2") (pintype "passive"))
      (node (ref "L9") (pin "2") (pinfunction "2_2") (pintype "passive"))
      (node (ref "R32") (pin "1") (pinfunction "1_1") (pintype "passive"))
      (node (ref "U9") (pin "38") (pinfunction "PMS_VO_38") (pintype "passive"))
    )
    (net (code "29") (name "Net-(U9-RFI)") (class "Default")
      (node (ref "L11") (pin "2") (pinfunction "2_2") (pintype "passive"))
      (node (ref "U9") (pin "12") (pinfunction "RFI_12") (pintype "passive"))
    )
    (net (code "30") (name "Net-(U9-RFO)") (class "Default")
      (node (ref "C55") (pin "1") (pinfunction "1_1") (pintype "passive"))
      (node (ref "L10") (pin "2") (pinfunction "2_2") (pintype "passive"))
      (node (ref "U9") (pin "11") (pinfunction "RFO_11") (pintype "passive"))
    )
    (net (code "31") (name "Net-(U9-RF_12VO_LDO)") (class "Default")
      (node (ref "C74") (pin "2") (pinfunction "2_2") (pintype "passive"))
      (node (ref "U9") (pin "17") (pinfunction "RF_12VO_LDO_17") (pintype "passive"))
    )
    (net (code "32") (name "Net-(U11-3V3OUT)") (class "Default")
      (node (ref "C67") (pin "2") (pinfunction "2_2") (pintype "passive"))
      (node (ref "C68") (pin "2") (pinfunction "2_2") (pintype "passive"))
      (node (ref "U11") (pin "3") (pinfunction "3V3OUT_3") (pintype "power_in"))
      (node (ref "U11") (pin "9") (pinfunction "VCCIO_9") (pintype "power_in"))
    )
    (net (code "33") (name "Net-(U11-RXD)") (class "Default")
      (node (ref "R38") (pin "1") (pinfunction "1_1") (pintype "passive"))
      (node (ref "U11") (pin "10") (pinfunction "RXD_10") (pintype "output"))
    )
    (net (code "34") (name "Net-(U11-TXD)") (class "Default")
      (node (ref "R37") (pin "1") (pinfunction "1_1") (pintype "passive"))
      (node (ref "U11") (pin "7") (pinfunction "TXD_7") (pintype "output"))
    )
    (net (code "35") (name "Net-(U11-~{RESET})") (class "Default")
      (node (ref "C66") (pin "1") (pinfunction "1_1") (pintype "passive"))
      (node (ref "R47") (pin "2") (pinfunction "2_2") (pintype "passive"))
      (node (ref "R48") (pin "2") (pinfunction "2_2") (pintype "passive"))
      (node (ref "U11") (pin "2") (pinfunction "~{RESET}_2") (pintype "input"))
    )
    (net (code "36") (name "Net-(U15-OUT1)") (class "Default")
      (node (ref "C78") (pin "2") (pinfunction "2_2") (pintype "passive"))
      (node (ref "U15") (pin "1") (pinfunction "OUT1_1") (pintype "output"))
    )
    (net (code "37") (name "Net-(U15-OUT2)") (class "Default")
      (node (ref "C76") (pin "2") (pinfunction "2_2") (pintype "passive"))
      (node (ref "U15") (pin "3") (pinfunction "OUT2_3") (pintype "output"))
    )
    (net (code "38") (name "Net-(U15-RFC)") (class "Default")
      (node (ref "C79") (pin "1") (pinfunction "1_1") (pintype "passive"))
      (node (ref "U15") (pin "5") (pinfunction "RFC_5") (pintype "passive"))
    )
    (net (code "39") (name "Net-(U16-OUTPUT)") (class "Default")
      (node (ref "C77") (pin "1") (pinfunction "1_1") (pintype "passive"))
      (node (ref "U16") (pin "5") (pinfunction "OUTPUT_5") (pintype "passive"))
    )
    (net (code "40") (name "Net-(U18-CS#)") (class "Default")
      (node (ref "R66") (pin "2") (pinfunction "2_2") (pintype "passive"))
      (node (ref "U18") (pin "1") (pinfunction "CS#_1") (pintype "input"))
    )
    (net (code "41") (name "Net-(U18-HOLD#{slash}SIO3)") (class "Default")
      (node (ref "R64") (pin "1") (pinfunction "1_1") (pintype "passive"))
      (node (ref "U18") (pin "7") (pinfunction "HOLD#/SIO3_7") (pintype "bidirectional"))
    )
    (net (code "42") (name "Net-(U18-SCLK)") (class "Default")
      (node (ref "R68") (pin "2") (pinfunction "2_2") (pintype "passive"))
      (node (ref "U18") (pin "6") (pinfunction "SCLK_6") (pintype "input"))
    )
    (net (code "43") (name "Net-(U18-SI{slash}SIO0)") (class "Default")
      (node (ref "R69") (pin "1") (pinfunction "1_1") (pintype "passive"))
      (node (ref "U18") (pin "5") (pinfunction "SI/SIO0_5") (pintype "bidirectional"))
    )
    (net (code "44") (name "Net-(U18-SO{slash}SIO1)") (class "Default")
      (node (ref "R67") (pin "1") (pinfunction "1_1") (pintype "passive"))
      (node (ref "U18") (pin "2") (pinfunction "SO/SIO1_2") (pintype "bidirectional"))
    )
    (net (code "45") (name "Net-(U18-WP#{slash}SIO2)") (class "Default")
      (node (ref "R65") (pin "1") (pinfunction "1_1") (pintype "passive"))
      (node (ref "U18") (pin "3") (pinfunction "WP#/SIO2_3") (pintype "bidirectional"))
    )
    (net (code "46") (name "P1V1_RX") (class "Default")
      (node (ref "C45") (pin "2") (pinfunction "2_2") (pintype "passive"))
      (node (ref "C47") (pin "2") (pinfunction "2_2") (pintype "passive"))
      (node (ref "U9") (pin "1") (pinfunction "VDDC_1") (pintype "passive"))
      (node (ref "U9") (pin "33") (pinfunction "VDDC_33") (pintype "passive"))
      (node (ref "U9") (pin "34") (pinfunction "PMS_VO_LDO_34") (pintype "passive"))
    )
    (net (code "47") (name "P1V45_RX") (class "Default")
      (node (ref "C41") (pin "1") (pinfunction "1_1") (pintype "passive"))
      (node (ref "C65") (pin "2") (pinfunction "2_2") (pintype "passive"))
      (node (ref "R32") (pin "2") (pinfunction "2_2") (pintype "passive"))
      (node (ref "U9") (pin "14") (pinfunction "RF_14VI_14") (pintype "passive"))
    )
    (net (code "48") (name "RX_32MHz") (class "Default")
      (node (ref "U9") (pin "15") (pinfunction "XTAL_IN_15") (pintype "passive"))
    )
    (net (code "49") (name "RX_FTDI_RXD") (class "Default")
      (node (ref "R38") (pin "2") (pinfunction "2_2") (pintype "passive"))
      (node (ref "U10") (pin "10") (pinfunction "NC1_10") (pintype "passive"))
    )
    (net (code "50") (name "RX_FTDI_TXD") (class "Default")
      (node (ref "R37") (pin "2") (pinfunction "2_2") (pintype "passive"))
      (node (ref "U10") (pin "8") (pinfunction "NC2_8") (pintype "passive"))
    )
    (net (code "51") (name "RX_GP15") (class "Default")
      (node (ref "U14") (pin "2") (pinfunction "A_2") (pintype "input"))
      (node (ref "U15") (pin "6") (pinfunction "VCTL1_6") (pintype "power_in"))
      (node (ref "U9") (pin "20") (pinfunction "GP15_/_RX_SEL_/_RF_TEST2_20") (pintype "passive"))
    )
    (net (code "52") (name "RX_GP15_INV") (class "Default")
      (node (ref "U14") (pin "4") (pinfunction "Y_4") (pintype "output"))
      (node (ref "U15") (pin "4") (pinfunction "VCTL2_4") (pintype "power_in"))
    )
    (net (code "53") (name "RX_GP16") (class "Default")
      (node (ref "U9") (pin "21") (pinfunction "GP16_/_PWR_DN_/_RF_TEST3_21") (pintype "passive"))
    )
    (net (code "54") (name "RX_GP17") (class "Default")
      (node (ref "U9") (pin "18") (pinfunction "GP17_/_ADCIN0_/_RF_TEST0_18") (pintype "passive"))
    )
    (net (code "55") (name "RX_GP18") (class "Default")
      (node (ref "U9") (pin "19") (pinfunction "GP18_/_ADCIN1_/_RF_TEST1_19") (pintype "passive"))
    )
    (net (code "56") (name "RX_GP20") (class "Default")
      (node (ref "P2") (pin "5") (pinfunction "5_5") (pintype "passive"))
      (node (ref "U9") (pin "7") (pinfunction "GP20_7") (pintype "passive"))
    )
    (net (code "57") (name "RX_GP24") (class "Default")
      (node (ref "U9") (pin "22") (pinfunction "GP24_/_PA_EN_22") (pintype "passive"))
    )
    (net (code "58") (name "RX_GP25") (class "Default")
      (node (ref "D5") (pin "1") (pinfunction "C_1") (pintype "passive"))
      (node (ref "U9") (pin "23") (pinfunction "GP25_23") (pintype "passive"))
    )
    (net (code "59") (name "RX_HSPI_CS_N") (class "Default")
      (node (ref "R35") (pin "1") (pinfunction "1_1") (pintype "passive"))
      (node (ref "U9") (pin "41") (pinfunction "HSPI_CS_N_/_GP28_41") (pintype "passive"))
    )
    (net (code "60") (name "RX_HSPI_EIRQ_N") (class "Default")
      (node (ref "R36") (pin "1") (pinfunction "1_1") (pintype "passive"))
      (node (ref "U9") (pin "47") (pinfunction "HSPI_EIRQ_N_/_GP30_47") (pintype "passive"))
    )
    (net (code "61") (name "RX_HSPI_MISO") (class "Default")
      (node (ref "U9") (pin "42") (pinfunction "HSPI_MISO_/_GP29_42") (pintype "passive"))
    )
    (net (code "62") (name "RX_HSPI_MOSI") (class "Default")
      (node (ref "U9") (pin "43") (pinfunction "HSPI_MOSI_/_GP06_43") (pintype "passive"))
    )
    (net (code "63") (name "RX_HSPI_SCLK") (class "Default")
      (node (ref "U9") (pin "44") (pinfunction "HSPI_CLK_/_GP07_44") (pintype "passive"))
    )
    (net (code "64") (name "RX_MODE") (class "Default")
      (node (ref "Q5") (pin "1") (pinfunction "G_1") (pintype "passive"))
      (node (ref "R58") (pin "1") (pinfunction "1_1") (pintype "passive"))
      (node (ref "SW6") (pin "2") (pinfunction "2_2") (pintype "passive"))
      (node (ref "U9") (pin "8") (pinfunction "MODE_/_GP19_8") (pintype "passive"))
    )
    (net (code "65") (name "RX_PMS_RST_N") (class "Default")
      (node (ref "C90") (pin "1") (pinfunction "1_1") (pintype "passive"))
      (node (ref "P2") (pin "2") (pinfunction "2_2") (pintype "passive"))
      (node (ref "Q6") (pin "3") (pinfunction "D_3") (pintype "passive"))
      (node (ref "R57") (pin "1") (pinfunction "1_1") (pintype "passive"))
      (node (ref "R59") (pin "2") (pinfunction "2_2") (pintype "passive"))
      (node (ref "SW5") (pin "1") (pinfunction "1_1") (pintype "passive"))
      (node (ref "SW5") (pin "2") (pinfunction "2_2") (pintype "passive"))
      (node (ref "U9") (pin "40") (pinfunction "RST_N_/_PMS_POR_N_40") (pintype "passive"))
    )
    (net (code "66") (name "RX_RFIO") (class "Default")
      (node (ref "C88") (pin "2") (pinfunction "2_2") (pintype "passive"))
      (node (ref "L14") (pin "2") (pinfunction "2_2") (pintype "passive"))
    )
    (net (code "67") (name "RX_RF_INPUT") (class "Default")
      (node (ref "C58") (pin "1") (pinfunction "1_1") (pintype "passive"))
      (node (ref "L11") (pin "1") (pinfunction "1_1") (pintype "passive"))
      (node (ref "U16") (pin "2") (pinfunction "INPUT_2") (pintype "passive"))
    )
    (net (code "68") (name "RX_RF_OUTPUT") (class "Default")
      (node (ref "C54") (pin "1") (pinfunction "1_1") (pintype "passive"))
      (node (ref "C76") (pin "1") (pinfunction "1_1") (pintype "passive"))
      (node (ref "L10") (pin "1") (pinfunction "1_1") (pintype "passive"))
    )
    (net (code "69") (name "RX_SWDCK") (class "Default")
      (node (ref "P2") (pin "6") (pinfunction "6_6") (pintype "passive"))
      (node (ref "R50") (pin "1") (pinfunction "1_1") (pintype "passive"))
      (node (ref "U9") (pin "2") (pinfunction "TCK_/_SWDCK_/_GP11_2") (pintype "passive"))
    )
    (net (code "70") (name "RX_SWDIO") (class "Default")
      (node (ref "P2") (pin "4") (pinfunction "4_4") (pintype "passive"))
      (node (ref "R51") (pin "1") (pinfunction "1_1") (pintype "passive"))
      (node (ref "U9") (pin "48") (pinfunction "TMS_/_SWDIO_/_GP10_48") (pintype "passive"))
    )
    (net (code "71") (name "RX_TDI") (class "Default")
      (node (ref "P2") (pin "10") (pinfunction "10_10") (pintype "passive"))
      (node (ref "U9") (pin "4") (pinfunction "TDI_/_GP13_4") (pintype "passive"))
    )
    (net (code "72") (name "RX_TDO") (class "Default")
      (node (ref "P2") (pin "8") (pinfunction "8_8") (pintype "passive"))
      (node (ref "U9") (pin "3") (pinfunction "TDO_/_GP12_3") (pintype "passive"))
    )
    (net (code "73") (name "RX_TRST_N") (class "Default")
      (node (ref "P2") (pin "7") (pinfunction "7_7") (pintype "passive"))
      (node (ref "R49") (pin "1") (pinfunction "1_1") (pintype "passive"))
      (node (ref "R53") (pin "2") (pinfunction "2_2") (pintype "passive"))
      (node (ref "U9") (pin "5") (pinfunction "GP14_/_TRST_N_5") (pintype "passive"))
    )
    (net (code "74") (name "RX_UART0_RXD") (class "Default")
      (node (ref "U10") (pin "7") (pinfunction "COM2_7") (pintype "passive"))
      (node (ref "U9") (pin "46") (pinfunction "UART0_RXD_/_GP09_46") (pintype "passive"))
    )
    (net (code "75") (name "RX_UART0_SEL") (class "Default")
      (node (ref "Q4") (pin "1") (pinfunction "G_1") (pintype "passive"))
      (node (ref "R54") (pin "1") (pinfunction "1_1") (pintype "passive"))
      (node (ref "R55") (pin "1") (pinfunction "1_1") (pintype "passive"))
      (node (ref "SW4") (pin "2") (pinfunction "2_2") (pintype "passive"))
      (node (ref "U10") (pin "1") (pinfunction "SEL1_1") (pintype "input"))
      (node (ref "U10") (pin "5") (pinfunction "SEL2_5") (pintype "input"))
    )
    (net (code "76") (name "RX_UART0_TXD") (class "Default")
      (node (ref "U10") (pin "11") (pinfunction "COM1_11") (pintype "passive"))
      (node (ref "U9") (pin "45") (pinfunction "UART0_TXD_/_GP08_45") (pintype "passive"))
    )
    (net (code "77") (name "RX_USB_D_N") (class "Default")
      (node (ref "U11") (pin "1") (pinfunction "USBDM_1") (pintype "bidirectional"))
    )
    (net (code "78") (name "RX_USB_D_P") (class "Default")
      (node (ref "U11") (pin "12") (pinfunction "USBDP_12") (pintype "bidirectional"))
    )
    (net (code "79") (name "SW_RX_RST") (class "Default")
      (node (ref "Q6") (pin "1") (pinfunction "G_1") (pintype "passive"))
      (node (ref "R62") (pin "2") (pinfunction "2_2") (pintype "passive"))
    )
    (net (code "80") (name "unconnected-(U9-XTAL_OUT-Pad16)") (class "Default")
      (node (ref "U9") (pin "16") (pinfunction "XTAL_OUT_16") (pintype "passive"))
    )
    (net (code "81") (name "unconnected-(U11-CBUS0-Pad6)") (class "Default")
      (node (ref "U11") (pin "6") (pinfunction "CBUS0_6") (pintype "bidirectional"))
    )
    (net (code "82") (name "unconnected-(U11-~{CTS}-Pad11)") (class "Default")
      (node (ref "U11") (pin "11") (pinfunction "~{CTS}_11") (pintype "input"))
    )
    (net (code "83") (name "unconnected-(U11-~{RTS}-Pad8)") (class "Default")
      (node (ref "U11") (pin "8") (pinfunction "~{RTS}_8") (pintype "input"))
    )
    (net (code "84") (name "unconnected-(U14B-NC-Pad1)") (class "Default")
      (node (ref "U14") (pin "1") (pinfunction "NC_1") (pintype "passive"))
    )
  )
)
